# CH32V002A4M6.net
KiCad netlist of a schematic drawn in Altium Designer
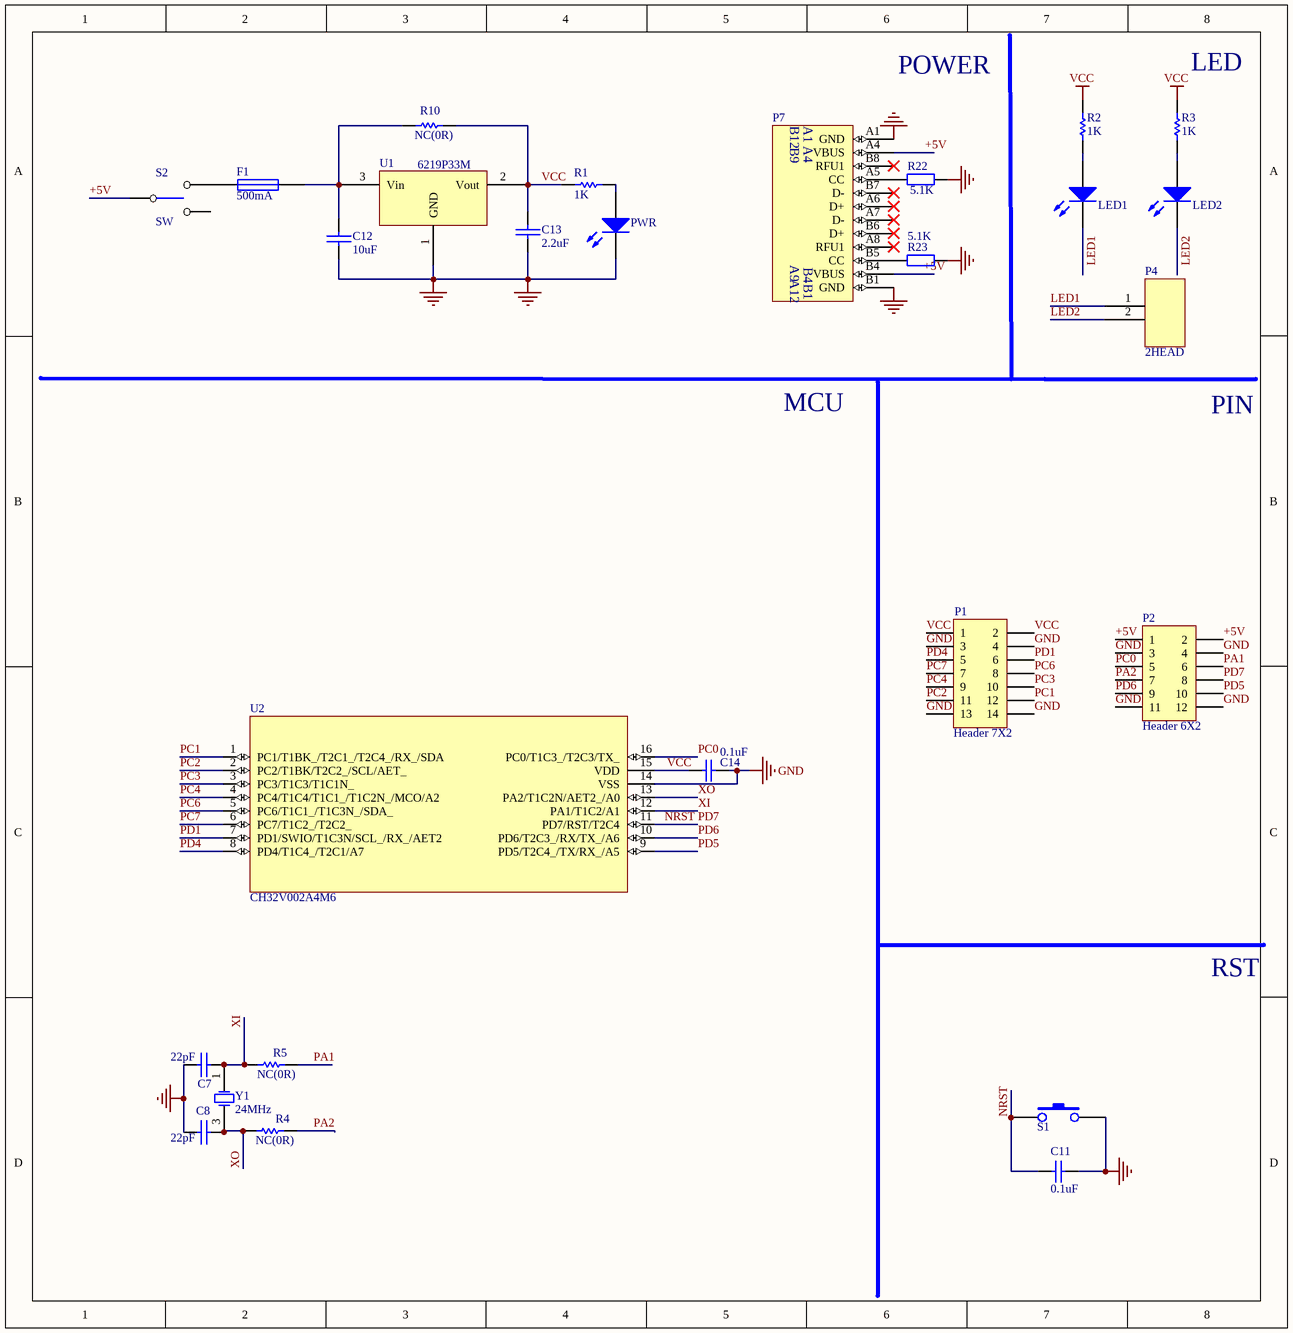
[diagram p0: CH32V002A4M6.SchDoc]

(export (version "E")
  (design (tool "Eeschema 10.0.6"))
  (components
    (comp (ref "C7")
      (value "22pF")
      (footprint "0402_C")
      (description "Capacitor")
      (libsource (lib "*") (part "CAP"))
    )
    (comp (ref "C8")
      (value "22pF")
      (footprint "0402_C")
      (description "Capacitor")
      (libsource (lib "*") (part "CAP"))
    )
    (comp (ref "C11")
      (value "0.1uF")
      (footprint "0402_C")
      (description "Capacitor")
      (fields (field (name "PUBLISHER") "Altium Limited"))
      (libsource (lib "*") (part "Cap"))
    )
    (comp (ref "C12")
      (value "10uF")
      (footprint "0603_C")
      (description "Capacitor")
      (libsource (lib "wch_sch_others") (part "CAP"))
    )
    (comp (ref "C13")
      (value "2.2uF")
      (footprint "0402_C")
      (description "Capacitor")
      (libsource (lib "wch_sch_others") (part "CAP"))
    )
    (comp (ref "C14")
      (value "0.1uF")
      (footprint "0603_C")
      (description "Capacitor")
      (fields (field (name "PUBLISHER") "Altium Limited"))
      (libsource (lib "*") (part "Cap"))
    )
    (comp (ref "F1")
      (value "500mA")
      (footprint "0603")
      (description "Fuse")
      (libsource (lib "*") (part "FUSE1"))
    )
    (comp (ref "LED1")
      (value "LED1   blue")
      (footprint "0603+")
      (description "Typical INFRARED GaAs LED")
      (fields (field (name "PUBLISHER") "Altium Limited"))
      (libsource (lib "") (part "LED0_1"))
    )
    (comp (ref "LED2")
      (value "LED2  blue")
      (footprint "0603+")
      (description "Typical INFRARED GaAs LED")
      (fields (field (name "PUBLISHER") "Altium Limited"))
      (libsource (lib "") (part "LED0_1"))
    )
    (comp (ref "P1")
      (value "Header 7X2")
      (footprint "HDR2X7")
      (description "Header, 7-Pin, Dual row")
      (fields (field (name "PUBLISHER") "Altium Limited"))
      (libsource (lib "Miscellaneous Connectors") (part "Header 7X2"))
    )
    (comp (ref "P2")
      (value "Header 6X2")
      (footprint "HDR2X6")
      (description "Header, 6-Pin, Dual row")
      (fields (field (name "PUBLISHER") "Altium Limited"))
      (libsource (lib "Miscellaneous Connectors") (part "Header 6X2"))
    )
    (comp (ref "P4") (value "2HEAD") (footprint "SIP2-2.54mm") (libsource (lib "*") (part "2HEAD")))
    (comp (ref "P7")
      (value "TYPE-C")
      (footprint "TYPE-C-Receptacle-2.0")
      (libsource (lib "*") (part "TYPE-C1"))
    )
    (comp (ref "PWR")
      (value "POWER  red")
      (footprint "0603+")
      (description "Typical INFRARED GaAs LED")
      (fields (field (name "PUBLISHER") "Altium Limited"))
      (libsource (lib "*") (part "LED0"))
    )
    (comp (ref "R1")
      (value "1K")
      (footprint "0402")
      (description "Semiconductor Resistor")
      (fields (field (name "PUBLISHER") "Altium Limited"))
      (libsource (lib "*") (part "Res Semi"))
    )
    (comp (ref "R2")
      (value "1K")
      (footprint "0402")
      (description "Semiconductor Resistor")
      (fields (field (name "PUBLISHER") "Altium Limited"))
      (libsource (lib "*") (part "Res Semi"))
    )
    (comp (ref "R3")
      (value "1K")
      (footprint "0402")
      (description "Semiconductor Resistor")
      (fields (field (name "PUBLISHER") "Altium Limited"))
      (libsource (lib "*") (part "Res Semi"))
    )
    (comp (ref "R4")
      (value "NC(0R)")
      (footprint "0402")
      (description "Semiconductor Resistor")
      (fields (field (name "Comment") "0R") (field (name "PUBLISHER") "Altium Limited"))
      (libsource (lib "*") (part "Res Semi"))
    )
    (comp (ref "R5")
      (value "NC(0R)")
      (footprint "0402")
      (description "Semiconductor Resistor")
      (fields (field (name "Comment") "0R") (field (name "PUBLISHER") "Altium Limited"))
      (libsource (lib "*") (part "Res Semi"))
    )
    (comp (ref "R10")
      (value "NC(0R)")
      (footprint "0402")
      (description "Semiconductor Resistor")
      (fields (field (name "Comment") "0R") (field (name "PUBLISHER") "Altium Limited"))
      (libsource (lib "*") (part "Res Semi"))
    )
    (comp (ref "R22")
      (value "5.1K")
      (footprint "0402")
      (description "Resistor")
      (libsource (lib "Miscellaneous Devices") (part "Res2"))
    )
    (comp (ref "R23")
      (value "5.1K")
      (footprint "0402")
      (description "Resistor")
      (libsource (lib "Miscellaneous Devices") (part "Res2"))
    )
    (comp (ref "S1") (value "NRST") (footprint "SMD_6.1x3.65x2.5mm-KEY") (libsource (lib "*") (part "KEY")))
    (comp (ref "S2") (value "SW") (footprint "SW1") (libsource (lib "*") (part "SW")))
    (comp (ref "U1")
      (value "6219P33M")
      (footprint "SOT-23")
      (libsource (lib "wch_sch_others") (part "6219P33M"))
    )
    (comp (ref "U2")
      (value "CH32V002A4M6")
      (footprint "SOP16")
      (description "RISC-V MCU, 48MHz, ADC/UART/I2C")
      (libsource (lib "DHXXXSCH") (part "CH32V002A4M6"))
    )
    (comp (ref "Y1")
      (value "24MHz")
      (footprint "XT3225")
      (description "Crystal Oscillator")
      (fields (field (name "PUBLISHER") "Altium Limited"))
      (libsource (lib "*") (part "XTAL"))
    )
  )
  (nets
    (net (code "1") (name "/+5V") (class "Default")
      (node (ref "P2") (pin "1") (pinfunction "1_1") (pintype "passive"))
      (node (ref "P2") (pin "2") (pinfunction "2_2") (pintype "passive"))
      (node (ref "P7") (pin "A4") (pinfunction "VBUS_A4") (pintype "bidirectional"))
      (node (ref "P7") (pin "B4") (pinfunction "VBUS_B4") (pintype "bidirectional"))
      (node (ref "S2") (pin "1") (pinfunction "1_1") (pintype "passive"))
    )
    (net (code "2") (name "/LED1") (class "Default")
      (node (ref "LED1") (pin "2") (pinfunction "K_2") (pintype "passive"))
      (node (ref "P4") (pin "1") (pintype "passive"))
    )
    (net (code "3") (name "/LED2") (class "Default")
      (node (ref "LED2") (pin "2") (pinfunction "K_2") (pintype "passive"))
      (node (ref "P4") (pin "2") (pintype "passive"))
    )
    (net (code "4") (name "/NRST") (class "Default")
      (node (ref "C11") (pin "2") (pinfunction "2_2") (pintype "passive"))
      (node (ref "P2") (pin "8") (pinfunction "8_8") (pintype "passive"))
      (node (ref "S1") (pin "1") (pinfunction "1_1") (pintype "passive"))
      (node (ref "U2") (pin "11") (pinfunction "PD7/RST/T2C4_11") (pintype "bidirectional"))
    )
    (net (code "5") (name "/PA1") (class "Default")
      (node (ref "P2") (pin "6") (pinfunction "6_6") (pintype "passive"))
      (node (ref "R5") (pin "2") (pinfunction "2_2") (pintype "passive"))
    )
    (net (code "6") (name "/PA2") (class "Default")
      (node (ref "P2") (pin "7") (pinfunction "7_7") (pintype "passive"))
      (node (ref "R4") (pin "2") (pinfunction "2_2") (pintype "passive"))
    )
    (net (code "7") (name "/PC0") (class "Default")
      (node (ref "P2") (pin "5") (pinfunction "5_5") (pintype "passive"))
      (node (ref "U2") (pin "16") (pinfunction "PC0/T1C3_/T2C3/TX__16") (pintype "bidirectional"))
    )
    (net (code "8") (name "/PC1") (class "Default")
      (node (ref "P1") (pin "12") (pinfunction "12_12") (pintype "passive"))
      (node (ref "U2") (pin "1") (pinfunction "PC1/T1BK_/T2C1_/T2C4_/RX_/SDA_1") (pintype "bidirectional"))
    )
    (net (code "9") (name "/PC2") (class "Default")
      (node (ref "P1") (pin "11") (pinfunction "11_11") (pintype "passive"))
      (node (ref "U2") (pin "2") (pinfunction "PC2/T1BK/T2C2_/SCL/AET__2") (pintype "bidirectional"))
    )
    (net (code "10") (name "/PC3") (class "Default")
      (node (ref "P1") (pin "10") (pinfunction "10_10") (pintype "passive"))
      (node (ref "U2") (pin "3") (pinfunction "PC3/T1C3/T1C1N__3") (pintype "bidirectional"))
    )
    (net (code "11") (name "/PC4") (class "Default")
      (node (ref "P1") (pin "9") (pinfunction "9_9") (pintype "passive"))
      (node (ref "U2") (pin "4") (pinfunction "PC4/T1C4/T1C1_/T1C2N_/MCO/A2_4") (pintype "bidirectional"))
    )
    (net (code "12") (name "/PC6") (class "Default")
      (node (ref "P1") (pin "8") (pinfunction "8_8") (pintype "passive"))
      (node (ref "U2") (pin "5") (pinfunction "PC6/T1C1_/T1C3N_/SDA__5") (pintype "bidirectional"))
    )
    (net (code "13") (name "/PC7") (class "Default")
      (node (ref "P1") (pin "7") (pinfunction "7_7") (pintype "passive"))
      (node (ref "U2") (pin "6") (pinfunction "PC7/T1C2_/T2C2__6") (pintype "bidirectional"))
    )
    (net (code "14") (name "/PD1") (class "Default")
      (node (ref "P1") (pin "6") (pinfunction "6_6") (pintype "passive"))
      (node (ref "U2") (pin "7") (pinfunction "PD1/SWIO/T1C3N/SCL_/RX_/AET2_7") (pintype "bidirectional"))
    )
    (net (code "15") (name "/PD4") (class "Default")
      (node (ref "P1") (pin "5") (pinfunction "5_5") (pintype "passive"))
      (node (ref "U2") (pin "8") (pinfunction "PD4/T1C4_/T2C1/A7_8") (pintype "bidirectional"))
    )
    (net (code "16") (name "/PD5") (class "Default")
      (node (ref "P2") (pin "10") (pinfunction "10_10") (pintype "passive"))
      (node (ref "U2") (pin "9") (pinfunction "PD5/T2C4_/TX/RX_/A5_9") (pintype "bidirectional"))
    )
    (net (code "17") (name "/PD6") (class "Default")
      (node (ref "P2") (pin "9") (pinfunction "9_9") (pintype "passive"))
      (node (ref "U2") (pin "10") (pinfunction "PD6/T2C3_/RX/TX_/A6_10") (pintype "bidirectional"))
    )
    (net (code "18") (name "/XI") (class "Default")
      (node (ref "C7") (pin "2") (pinfunction "2_2") (pintype "passive"))
      (node (ref "R5") (pin "1") (pinfunction "1_1") (pintype "passive"))
      (node (ref "U2") (pin "12") (pinfunction "PA1/T1C2/A1_12") (pintype "bidirectional"))
      (node (ref "Y1") (pin "1") (pinfunction "OSC1_1") (pintype "passive"))
    )
    (net (code "19") (name "/XO") (class "Default")
      (node (ref "C8") (pin "2") (pinfunction "2_2") (pintype "passive"))
      (node (ref "R4") (pin "1") (pinfunction "1_1") (pintype "passive"))
      (node (ref "U2") (pin "13") (pinfunction "PA2/T1C2N/AET2_/A0_13") (pintype "bidirectional"))
      (node (ref "Y1") (pin "3") (pinfunction "OSC2_3") (pintype "passive"))
    )
    (net (code "20") (name "GND") (class "Default")
      (node (ref "C11") (pin "1") (pinfunction "1_1") (pintype "passive"))
      (node (ref "C12") (pin "2") (pinfunction "2_2") (pintype "passive"))
      (node (ref "C13") (pin "1") (pinfunction "1_1") (pintype "passive"))
      (node (ref "C14") (pin "2") (pinfunction "2_2") (pintype "passive"))
      (node (ref "C7") (pin "1") (pinfunction "1_1") (pintype "passive"))
      (node (ref "C8") (pin "1") (pinfunction "1_1") (pintype "passive"))
      (node (ref "P1") (pin "13") (pinfunction "13_13") (pintype "passive"))
      (node (ref "P1") (pin "14") (pinfunction "14_14") (pintype "passive"))
      (node (ref "P1") (pin "3") (pinfunction "3_3") (pintype "passive"))
      (node (ref "P1") (pin "4") (pinfunction "4_4") (pintype "passive"))
      (node (ref "P2") (pin "11") (pinfunction "11_11") (pintype "passive"))
      (node (ref "P2") (pin "12") (pinfunction "12_12") (pintype "passive"))
      (node (ref "P2") (pin "3") (pinfunction "3_3") (pintype "passive"))
      (node (ref "P2") (pin "4") (pinfunction "4_4") (pintype "passive"))
      (node (ref "P7") (pin "A1") (pinfunction "GND_A1") (pintype "bidirectional"))
      (node (ref "P7") (pin "B1") (pinfunction "GND_B1") (pintype "bidirectional"))
      (node (ref "PWR") (pin "2") (pinfunction "K_2") (pintype "passive"))
      (node (ref "R22") (pin "2") (pinfunction "2_2") (pintype "passive"))
      (node (ref "R23") (pin "2") (pinfunction "2_2") (pintype "passive"))
      (node (ref "S1") (pin "2") (pinfunction "2_2") (pintype "passive"))
      (node (ref "U1") (pin "1") (pinfunction "GND_1") (pintype "passive"))
      (node (ref "U2") (pin "14") (pinfunction "VSS_14") (pintype "power_in"))
    )
    (net (code "21") (name "Net-(F1-Pad1)") (class "Default")
      (node (ref "F1") (pin "1") (pinfunction "1_1") (pintype "passive"))
      (node (ref "S2") (pin "3") (pinfunction "3_3") (pintype "passive"))
    )
    (net (code "22") (name "Net-(LED1-A)") (class "Default")
      (node (ref "LED1") (pin "1") (pinfunction "A_1") (pintype "passive"))
      (node (ref "R2") (pin "2") (pinfunction "2_2") (pintype "passive"))
    )
    (net (code "23") (name "Net-(LED2-A)") (class "Default")
      (node (ref "LED2") (pin "1") (pinfunction "A_1") (pintype "passive"))
      (node (ref "R3") (pin "2") (pinfunction "2_2") (pintype "passive"))
    )
    (net (code "24") (name "Net-(P7-CC-PadA5)") (class "Default")
      (node (ref "P7") (pin "A5") (pinfunction "CC_A5") (pintype "bidirectional"))
      (node (ref "R22") (pin "1") (pinfunction "1_1") (pintype "passive"))
    )
    (net (code "25") (name "Net-(P7-CC-PadB5)") (class "Default")
      (node (ref "P7") (pin "B5") (pinfunction "CC_B5") (pintype "bidirectional"))
      (node (ref "R23") (pin "1") (pinfunction "1_1") (pintype "passive"))
    )
    (net (code "26") (name "Net-(PWR-A)") (class "Default")
      (node (ref "PWR") (pin "1") (pinfunction "A_1") (pintype "passive"))
      (node (ref "R1") (pin "1") (pinfunction "1_1") (pintype "passive"))
    )
    (net (code "27") (name "Net-(U1-Vin)") (class "Default")
      (node (ref "C12") (pin "1") (pinfunction "1_1") (pintype "passive"))
      (node (ref "F1") (pin "2") (pinfunction "2_2") (pintype "passive"))
      (node (ref "R10") (pin "1") (pinfunction "1_1") (pintype "passive"))
      (node (ref "U1") (pin "3") (pinfunction "Vin_3") (pintype "passive"))
    )
    (net (code "28") (name "VCC") (class "Default")
      (node (ref "C13") (pin "2") (pinfunction "2_2") (pintype "passive"))
      (node (ref "C14") (pin "1") (pinfunction "1_1") (pintype "passive"))
      (node (ref "P1") (pin "1") (pinfunction "1_1") (pintype "passive"))
      (node (ref "P1") (pin "2") (pinfunction "2_2") (pintype "passive"))
      (node (ref "R1") (pin "2") (pinfunction "2_2") (pintype "passive"))
      (node (ref "R10") (pin "2") (pinfunction "2_2") (pintype "passive"))
      (node (ref "R2") (pin "1") (pinfunction "1_1") (pintype "passive"))
      (node (ref "R3") (pin "1") (pinfunction "1_1") (pintype "passive"))
      (node (ref "U1") (pin "2") (pinfunction "Vout_2") (pintype "passive"))
      (node (ref "U2") (pin "15") (pinfunction "VDD_15") (pintype "power_in"))
    )
    (net (code "29") (name "unconnected-(P7-D+-PadA6)") (class "Default")
      (node (ref "P7") (pin "A6") (pinfunction "D+_A6") (pintype "bidirectional+no_connect"))
    )
    (net (code "30") (name "unconnected-(P7-D+-PadB6)") (class "Default")
      (node (ref "P7") (pin "B6") (pinfunction "D+_B6") (pintype "bidirectional+no_connect"))
    )
    (net (code "31") (name "unconnected-(P7-D--PadA7)") (class "Default")
      (node (ref "P7") (pin "A7") (pinfunction "D-_A7") (pintype "bidirectional+no_connect"))
    )
    (net (code "32") (name "unconnected-(P7-D--PadB7)") (class "Default")
      (node (ref "P7") (pin "B7") (pinfunction "D-_B7") (pintype "bidirectional+no_connect"))
    )
    (net (code "33") (name "unconnected-(P7-RFU1-PadA8)") (class "Default")
      (node (ref "P7") (pin "A8") (pinfunction "RFU1_A8") (pintype "bidirectional+no_connect"))
    )
    (net (code "34") (name "unconnected-(P7-RFU1-PadB8)") (class "Default")
      (node (ref "P7") (pin "B8") (pinfunction "RFU1_B8") (pintype "bidirectional+no_connect"))
    )
    (net (code "35") (name "unconnected-(S2-Pad2)") (class "Default")
      (node (ref "S2") (pin "2") (pinfunction "2_2") (pintype "passive"))
    )
  )
)
